# sample_arduino.net
KiCad netlist of a schematic drawn in EAGLE
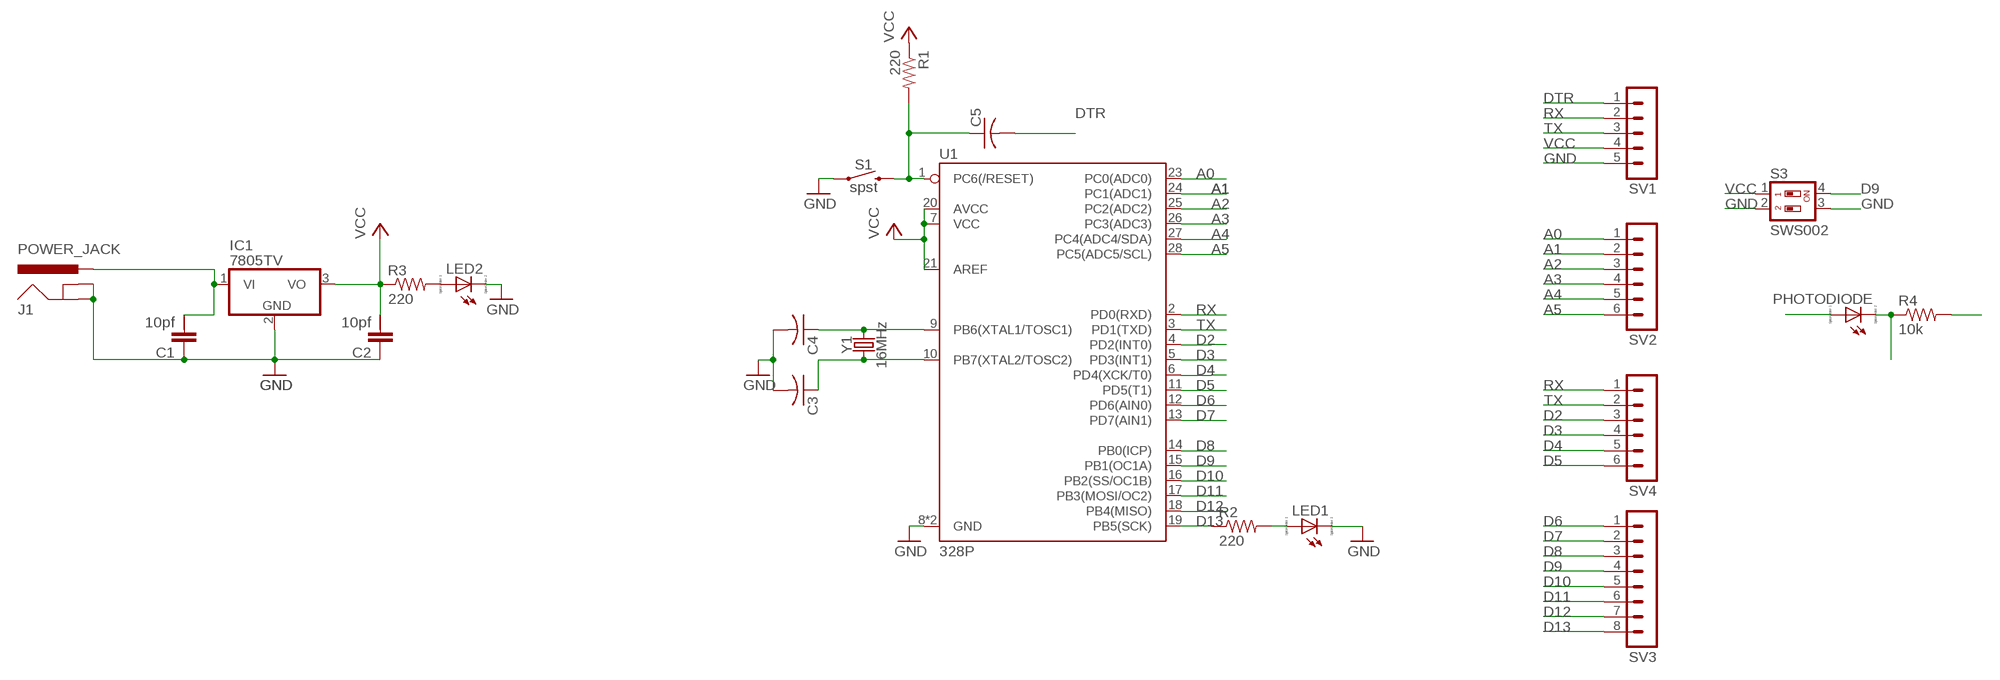
[diagram p0: schematic, sheet 1]

(export (version "E")
  (design (tool "Eeschema 10.0.6"))
  (components
    (comp (ref "C1")
      (value "10pf")
      (footprint "eagle-import:C2.5_5-6")
      (libsource (lib "eagle-import") (part "C-2.5-5/6"))
    )
    (comp (ref "C2")
      (value "10pf")
      (footprint "eagle-import:C2.5_5-6")
      (libsource (lib "eagle-import") (part "C-2.5-5/6"))
    )
    (comp (ref "C3")
      (value "C-US025-024X044")
      (footprint "eagle-import:C025-024X044")
      (libsource (lib "eagle-import") (part "C-US025-024X044"))
    )
    (comp (ref "C4")
      (value "C-US025-024X044")
      (footprint "eagle-import:C025-024X044")
      (libsource (lib "eagle-import") (part "C-US025-024X044"))
    )
    (comp (ref "C5")
      (value "C-US025-024X044")
      (footprint "eagle-import:C025-024X044")
      (libsource (lib "eagle-import") (part "C-US025-024X044"))
    )
    (comp (ref "IC1")
      (value "7805TV")
      (footprint "eagle-import:TO220V")
      (libsource (lib "eagle-import") (part "78TV05"))
    )
    (comp (ref "J1")
      (value "POWER_JACK")
      (footprint "eagle-import:POWER_JACK_PTH")
      (libsource (lib "eagle-import") (part "POWER_JACK"))
    )
    (comp (ref "LED1")
      (value "LED_ELD260")
      (footprint "eagle-import:LED_LD260")
      (libsource (lib "eagle-import") (part "LED_ELD260"))
    )
    (comp (ref "LED2")
      (value "LED_ELD260")
      (footprint "eagle-import:LED_LD260")
      (libsource (lib "eagle-import") (part "LED_ELD260"))
    )
    (comp (ref "PHOTODIODE")
      (value "LED_ELD260")
      (footprint "eagle-import:LED_LD260")
      (libsource (lib "eagle-import") (part "LED_ELD260"))
    )
    (comp (ref "R1")
      (value "220")
      (footprint "eagle-import:0204_7")
      (libsource (lib "eagle-import") (part "R-US_0204/7"))
    )
    (comp (ref "R2")
      (value "220")
      (footprint "eagle-import:0204_7")
      (libsource (lib "eagle-import") (part "R-US_0204/7"))
    )
    (comp (ref "R3")
      (value "220")
      (footprint "eagle-import:0204_7")
      (libsource (lib "eagle-import") (part "R-US_0204/7"))
    )
    (comp (ref "R4")
      (value "10k")
      (footprint "eagle-import:0204_7")
      (libsource (lib "eagle-import") (part "R-US_0204/7"))
    )
    (comp (ref "S1")
      (value "spst")
      (footprint "eagle-import:TACTILE_SWITCH_PTH_6.0MM")
      (libsource (lib "eagle-import") (part "MOMENTARY-SWITCH-SPST-PTH-6.0MM"))
    )
    (comp (ref "S3")
      (value "SWS002")
      (footprint "eagle-import:SMS-002")
      (libsource (lib "eagle-import") (part "SWS002"))
    )
    (comp (ref "SV1")
      (value "MA05-1")
      (footprint "eagle-import:MA05-1")
      (libsource (lib "eagle-import") (part "MA05-1"))
    )
    (comp (ref "SV2")
      (value "MA06-1")
      (footprint "eagle-import:MA06-1")
      (libsource (lib "eagle-import") (part "MA06-1"))
    )
    (comp (ref "SV3")
      (value "MA08-1")
      (footprint "eagle-import:MA08-1")
      (libsource (lib "eagle-import") (part "MA08-1"))
    )
    (comp (ref "SV4")
      (value "MA06-1")
      (footprint "eagle-import:MA06-1")
      (libsource (lib "eagle-import") (part "MA06-1"))
    )
    (comp (ref "U1")
      (value "328P")
      (footprint "eagle-import:DIP28")
      (libsource (lib "eagle-import") (part "ATMEGA328P_PDIP"))
    )
    (comp (ref "Y1")
      (value "16MHz")
      (footprint "eagle-import:HC49US")
      (libsource (lib "eagle-import") (part "CRYSTAL-16MHZPTH-HC49US"))
    )
  )
  (nets
    (net (code "1") (name "/A0") (class "Default")
      (node (ref "SV2") (pin "1") (pinfunction "1_1") (pintype "passive"))
      (node (ref "U1") (pin "23") (pinfunction "PC0(ADC0)_23") (pintype "bidirectional"))
    )
    (net (code "2") (name "/A1") (class "Default")
      (node (ref "SV2") (pin "2") (pinfunction "2_2") (pintype "passive"))
      (node (ref "U1") (pin "24") (pinfunction "PC1(ADC1)_24") (pintype "bidirectional"))
    )
    (net (code "3") (name "/A2") (class "Default")
      (node (ref "SV2") (pin "3") (pinfunction "3_3") (pintype "passive"))
      (node (ref "U1") (pin "25") (pinfunction "PC2(ADC2)_25") (pintype "bidirectional"))
    )
    (net (code "4") (name "/A3") (class "Default")
      (node (ref "SV2") (pin "4") (pinfunction "4_4") (pintype "passive"))
      (node (ref "U1") (pin "26") (pinfunction "PC3(ADC3)_26") (pintype "bidirectional"))
    )
    (net (code "5") (name "/A4") (class "Default")
      (node (ref "SV2") (pin "5") (pinfunction "5_5") (pintype "passive"))
      (node (ref "U1") (pin "27") (pinfunction "PC4(ADC4/SDA)_27") (pintype "bidirectional"))
    )
    (net (code "6") (name "/A5") (class "Default")
      (node (ref "PHOTODIODE") (pin "K") (pinfunction "C_K") (pintype "passive"))
      (node (ref "R4") (pin "1") (pinfunction "1_1") (pintype "passive"))
      (node (ref "SV2") (pin "6") (pinfunction "6_6") (pintype "passive"))
      (node (ref "U1") (pin "28") (pinfunction "PC5(ADC5/SCL)_28") (pintype "bidirectional"))
    )
    (net (code "7") (name "/D2") (class "Default")
      (node (ref "SV4") (pin "3") (pinfunction "3_3") (pintype "passive"))
      (node (ref "U1") (pin "4") (pinfunction "PD2(INT0)_4") (pintype "bidirectional"))
    )
    (net (code "8") (name "/D3") (class "Default")
      (node (ref "SV4") (pin "4") (pinfunction "4_4") (pintype "passive"))
      (node (ref "U1") (pin "5") (pinfunction "PD3(INT1)_5") (pintype "bidirectional"))
    )
    (net (code "9") (name "/D4") (class "Default")
      (node (ref "SV4") (pin "5") (pinfunction "5_5") (pintype "passive"))
      (node (ref "U1") (pin "6") (pinfunction "PD4(XCK/T0)_6") (pintype "bidirectional"))
    )
    (net (code "10") (name "/D5") (class "Default")
      (node (ref "SV4") (pin "6") (pinfunction "6_6") (pintype "passive"))
      (node (ref "U1") (pin "11") (pinfunction "PD5(T1)_11") (pintype "bidirectional"))
    )
    (net (code "11") (name "/D6") (class "Default")
      (node (ref "SV3") (pin "1") (pinfunction "1_1") (pintype "passive"))
      (node (ref "U1") (pin "12") (pinfunction "PD6(AIN0)_12") (pintype "bidirectional"))
    )
    (net (code "12") (name "/D7") (class "Default")
      (node (ref "SV3") (pin "2") (pinfunction "2_2") (pintype "passive"))
      (node (ref "U1") (pin "13") (pinfunction "PD7(AIN1)_13") (pintype "bidirectional"))
    )
    (net (code "13") (name "/D8") (class "Default")
      (node (ref "SV3") (pin "3") (pinfunction "3_3") (pintype "passive"))
      (node (ref "U1") (pin "14") (pinfunction "PB0(ICP)_14") (pintype "bidirectional"))
    )
    (net (code "14") (name "/D9") (class "Default")
      (node (ref "S3") (pin "4") (pinfunction "4_4") (pintype "passive"))
      (node (ref "SV3") (pin "4") (pinfunction "4_4") (pintype "passive"))
      (node (ref "U1") (pin "15") (pinfunction "PB1(OC1A)_15") (pintype "bidirectional"))
    )
    (net (code "15") (name "/D10") (class "Default")
      (node (ref "SV3") (pin "5") (pinfunction "5_5") (pintype "passive"))
      (node (ref "U1") (pin "16") (pinfunction "PB2(SS/OC1B)_16") (pintype "bidirectional"))
    )
    (net (code "16") (name "/D11") (class "Default")
      (node (ref "SV3") (pin "6") (pinfunction "6_6") (pintype "passive"))
      (node (ref "U1") (pin "17") (pinfunction "PB3(MOSI/OC2)_17") (pintype "bidirectional"))
    )
    (net (code "17") (name "/D12") (class "Default")
      (node (ref "SV3") (pin "7") (pinfunction "7_7") (pintype "passive"))
      (node (ref "U1") (pin "18") (pinfunction "PB4(MISO)_18") (pintype "bidirectional"))
    )
    (net (code "18") (name "/D13") (class "Default")
      (node (ref "R2") (pin "1") (pinfunction "1_1") (pintype "passive"))
      (node (ref "SV3") (pin "8") (pinfunction "8_8") (pintype "passive"))
      (node (ref "U1") (pin "19") (pinfunction "PB5(SCK)_19") (pintype "bidirectional"))
    )
    (net (code "19") (name "/DTR") (class "Default")
      (node (ref "C5") (pin "2") (pinfunction "2_2") (pintype "passive"))
      (node (ref "SV1") (pin "1") (pinfunction "1_1") (pintype "passive"))
    )
    (net (code "20") (name "/RX") (class "Default")
      (node (ref "SV1") (pin "2") (pinfunction "2_2") (pintype "passive"))
      (node (ref "SV4") (pin "1") (pinfunction "1_1") (pintype "passive"))
      (node (ref "U1") (pin "2") (pinfunction "PD0(RXD)_2") (pintype "bidirectional"))
    )
    (net (code "21") (name "/TX") (class "Default")
      (node (ref "SV1") (pin "3") (pinfunction "3_3") (pintype "passive"))
      (node (ref "SV4") (pin "2") (pinfunction "2_2") (pintype "passive"))
      (node (ref "U1") (pin "3") (pinfunction "PD1(TXD)_3") (pintype "bidirectional"))
    )
    (net (code "22") (name "GND") (class "Default")
      (node (ref "C1") (pin "1") (pinfunction "1_1") (pintype "passive"))
      (node (ref "C2") (pin "1") (pinfunction "1_1") (pintype "passive"))
      (node (ref "C3") (pin "2") (pinfunction "2_2") (pintype "passive"))
      (node (ref "C4") (pin "2") (pinfunction "2_2") (pintype "passive"))
      (node (ref "IC1") (pin "2") (pinfunction "GND_2") (pintype "passive"))
      (node (ref "J1") (pin "GND") (pinfunction "GND_GND") (pintype "bidirectional"))
      (node (ref "J1") (pin "GNDBREAK") (pinfunction "GNDBREAK_GNDBREAK") (pintype "bidirectional"))
      (node (ref "LED1") (pin "K") (pinfunction "C_K") (pintype "passive"))
      (node (ref "LED2") (pin "K") (pinfunction "C_K") (pintype "passive"))
      (node (ref "PHOTODIODE") (pin "A") (pinfunction "A_A") (pintype "passive"))
      (node (ref "S1") (pin "1") (pinfunction "1_1") (pintype "passive"))
      (node (ref "S3") (pin "2") (pinfunction "2_2") (pintype "passive"))
      (node (ref "S3") (pin "3") (pinfunction "3_3") (pintype "passive"))
      (node (ref "SV1") (pin "5") (pinfunction "5_5") (pintype "passive"))
      (node (ref "U1") (pin "22") (pinfunction "GND_22") (pintype "bidirectional"))
      (node (ref "U1") (pin "8") (pinfunction "GND_8") (pintype "bidirectional"))
    )
    (net (code "23") (name "Net-(IC1-VI)") (class "Default")
      (node (ref "C1") (pin "2") (pinfunction "2_2") (pintype "passive"))
      (node (ref "IC1") (pin "1") (pinfunction "VI_1") (pintype "input"))
      (node (ref "J1") (pin "PWR") (pinfunction "PWR_PWR") (pintype "bidirectional"))
    )
    (net (code "24") (name "Net-(LED1-PadA)") (class "Default")
      (node (ref "LED1") (pin "A") (pinfunction "A_A") (pintype "passive"))
      (node (ref "R2") (pin "2") (pinfunction "2_2") (pintype "passive"))
    )
    (net (code "25") (name "Net-(LED2-PadA)") (class "Default")
      (node (ref "LED2") (pin "A") (pinfunction "A_A") (pintype "passive"))
      (node (ref "R3") (pin "2") (pinfunction "2_2") (pintype "passive"))
    )
    (net (code "26") (name "Net-(S1-2)") (class "Default")
      (node (ref "C5") (pin "1") (pinfunction "1_1") (pintype "passive"))
      (node (ref "R1") (pin "2") (pinfunction "2_2") (pintype "passive"))
      (node (ref "S1") (pin "3") (pinfunction "2_3") (pintype "passive"))
      (node (ref "U1") (pin "1") (pinfunction "PC6(/RESET)_1") (pintype "bidirectional"))
    )
    (net (code "27") (name "Net-(U1-PB6(XTAL1{slash}TOSC1))") (class "Default")
      (node (ref "C4") (pin "1") (pinfunction "1_1") (pintype "passive"))
      (node (ref "U1") (pin "9") (pinfunction "PB6(XTAL1/TOSC1)_9") (pintype "bidirectional"))
      (node (ref "Y1") (pin "2") (pinfunction "2_2") (pintype "passive"))
    )
    (net (code "28") (name "Net-(U1-PB7(XTAL2{slash}TOSC2))") (class "Default")
      (node (ref "C3") (pin "1") (pinfunction "1_1") (pintype "passive"))
      (node (ref "U1") (pin "10") (pinfunction "PB7(XTAL2/TOSC2)_10") (pintype "bidirectional"))
      (node (ref "Y1") (pin "1") (pinfunction "1_1") (pintype "passive"))
    )
    (net (code "29") (name "VCC") (class "Default")
      (node (ref "C2") (pin "2") (pinfunction "2_2") (pintype "passive"))
      (node (ref "IC1") (pin "3") (pinfunction "VO_3") (pintype "passive"))
      (node (ref "R1") (pin "1") (pinfunction "1_1") (pintype "passive"))
      (node (ref "R3") (pin "1") (pinfunction "1_1") (pintype "passive"))
      (node (ref "R4") (pin "2") (pinfunction "2_2") (pintype "passive"))
      (node (ref "S3") (pin "1") (pinfunction "1_1") (pintype "passive"))
      (node (ref "SV1") (pin "4") (pinfunction "4_4") (pintype "passive"))
      (node (ref "U1") (pin "20") (pinfunction "AVCC_20") (pintype "bidirectional"))
      (node (ref "U1") (pin "21") (pinfunction "AREF_21") (pintype "bidirectional"))
      (node (ref "U1") (pin "7") (pinfunction "VCC_7") (pintype "bidirectional"))
    )
    (net (code "30") (name "unconnected-(C1-Pad3)") (class "Default")
      (node (ref "C1") (pin "3") (pinfunction "3_3") (pintype "passive"))
    )
    (net (code "31") (name "unconnected-(C2-Pad3)") (class "Default")
      (node (ref "C2") (pin "3") (pinfunction "3_3") (pintype "passive"))
    )
  )
)
